# TH1.net
KiCad netlist of a schematic drawn in Altium Designer
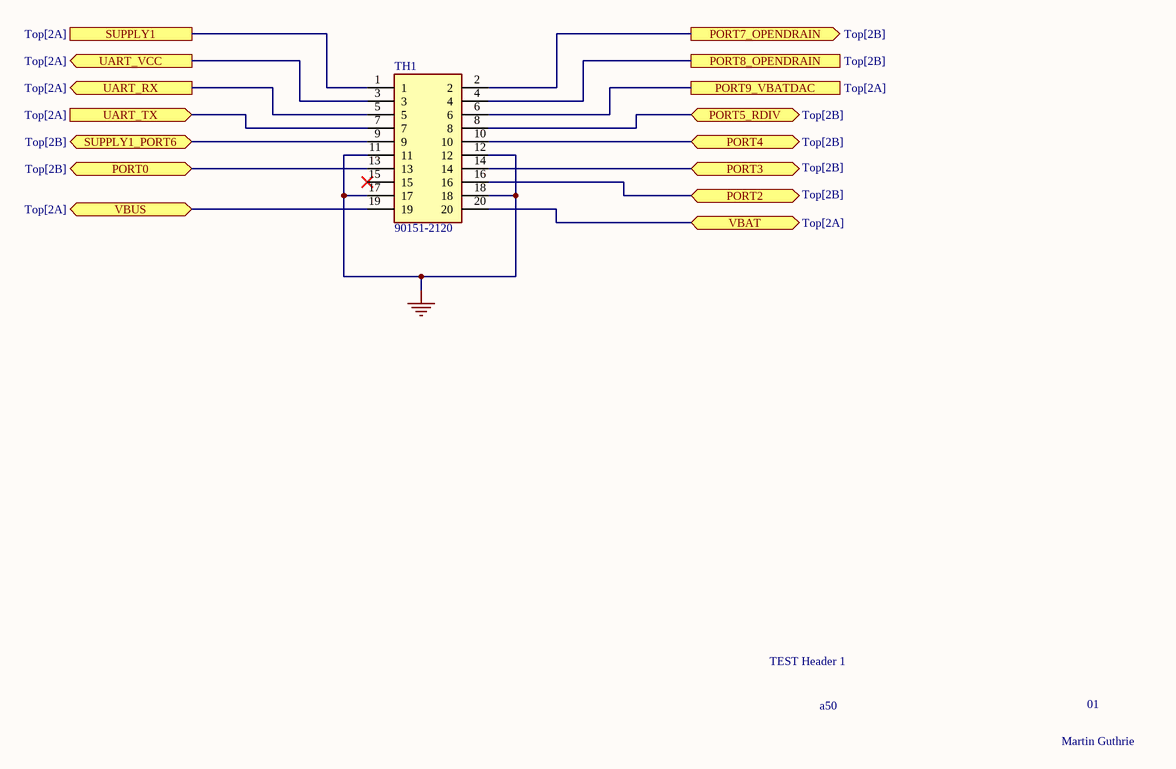
[diagram p0: TH1.SchDoc]

(export (version "E")
  (design (tool "Eeschema 10.0.6"))
  (components
    (comp (ref "TH1")
      (value "90151-2120")
      (footprint "PcbLib:90151-2120")
      (description "Connector")
      (fields (field (name "MOUSER PART NUMBER") "538-90151-2120"))
      (libsource (lib "SchematicLib") (part "90151-2120"))
    )
  )
  (nets
    (net (code "1") (name "/PORT0") (class "Default")
      (node (ref "TH1") (pin "13") (pinfunction "13_13") (pintype "passive"))
    )
    (net (code "2") (name "/PORT2") (class "Default")
      (node (ref "TH1") (pin "16") (pinfunction "16_16") (pintype "passive"))
    )
    (net (code "3") (name "/PORT3") (class "Default")
      (node (ref "TH1") (pin "14") (pinfunction "14_14") (pintype "passive"))
    )
    (net (code "4") (name "/PORT4") (class "Default")
      (node (ref "TH1") (pin "10") (pinfunction "10_10") (pintype "passive"))
    )
    (net (code "5") (name "/PORT5_RDIV") (class "Default")
      (node (ref "TH1") (pin "8") (pinfunction "8_8") (pintype "passive"))
    )
    (net (code "6") (name "/PORT7_OPENDRAIN") (class "Default")
      (node (ref "TH1") (pin "2") (pinfunction "2_2") (pintype "passive"))
    )
    (net (code "7") (name "/PORT8_OPENDRAIN") (class "Default")
      (node (ref "TH1") (pin "4") (pinfunction "4_4") (pintype "passive"))
    )
    (net (code "8") (name "/PORT9_VBATDAC") (class "Default")
      (node (ref "TH1") (pin "6") (pinfunction "6_6") (pintype "passive"))
    )
    (net (code "9") (name "/SUPPLY1") (class "Default")
      (node (ref "TH1") (pin "1") (pinfunction "1_1") (pintype "passive"))
    )
    (net (code "10") (name "/SUPPLY1_PORT6") (class "Default")
      (node (ref "TH1") (pin "9") (pinfunction "9_9") (pintype "passive"))
    )
    (net (code "11") (name "/UART_RX") (class "Default")
      (node (ref "TH1") (pin "5") (pinfunction "5_5") (pintype "passive"))
    )
    (net (code "12") (name "/UART_TX") (class "Default")
      (node (ref "TH1") (pin "7") (pinfunction "7_7") (pintype "passive"))
    )
    (net (code "13") (name "/UART_VCC") (class "Default")
      (node (ref "TH1") (pin "3") (pinfunction "3_3") (pintype "passive"))
    )
    (net (code "14") (name "/VBAT") (class "Default")
      (node (ref "TH1") (pin "20") (pinfunction "20_20") (pintype "passive"))
    )
    (net (code "15") (name "/VBUS") (class "Default")
      (node (ref "TH1") (pin "19") (pinfunction "19_19") (pintype "passive"))
    )
    (net (code "16") (name "GND") (class "Default")
      (node (ref "TH1") (pin "11") (pinfunction "11_11") (pintype "passive"))
      (node (ref "TH1") (pin "12") (pinfunction "12_12") (pintype "passive"))
      (node (ref "TH1") (pin "17") (pinfunction "17_17") (pintype "passive"))
      (node (ref "TH1") (pin "18") (pinfunction "18_18") (pintype "passive"))
    )
    (net (code "17") (name "unconnected-(TH1-Pad15)") (class "Default")
      (node (ref "TH1") (pin "15") (pinfunction "15_15") (pintype "passive+no_connect"))
    )
  )
)
